# Conn_A.net
KiCad netlist of a schematic drawn in Altium Designer
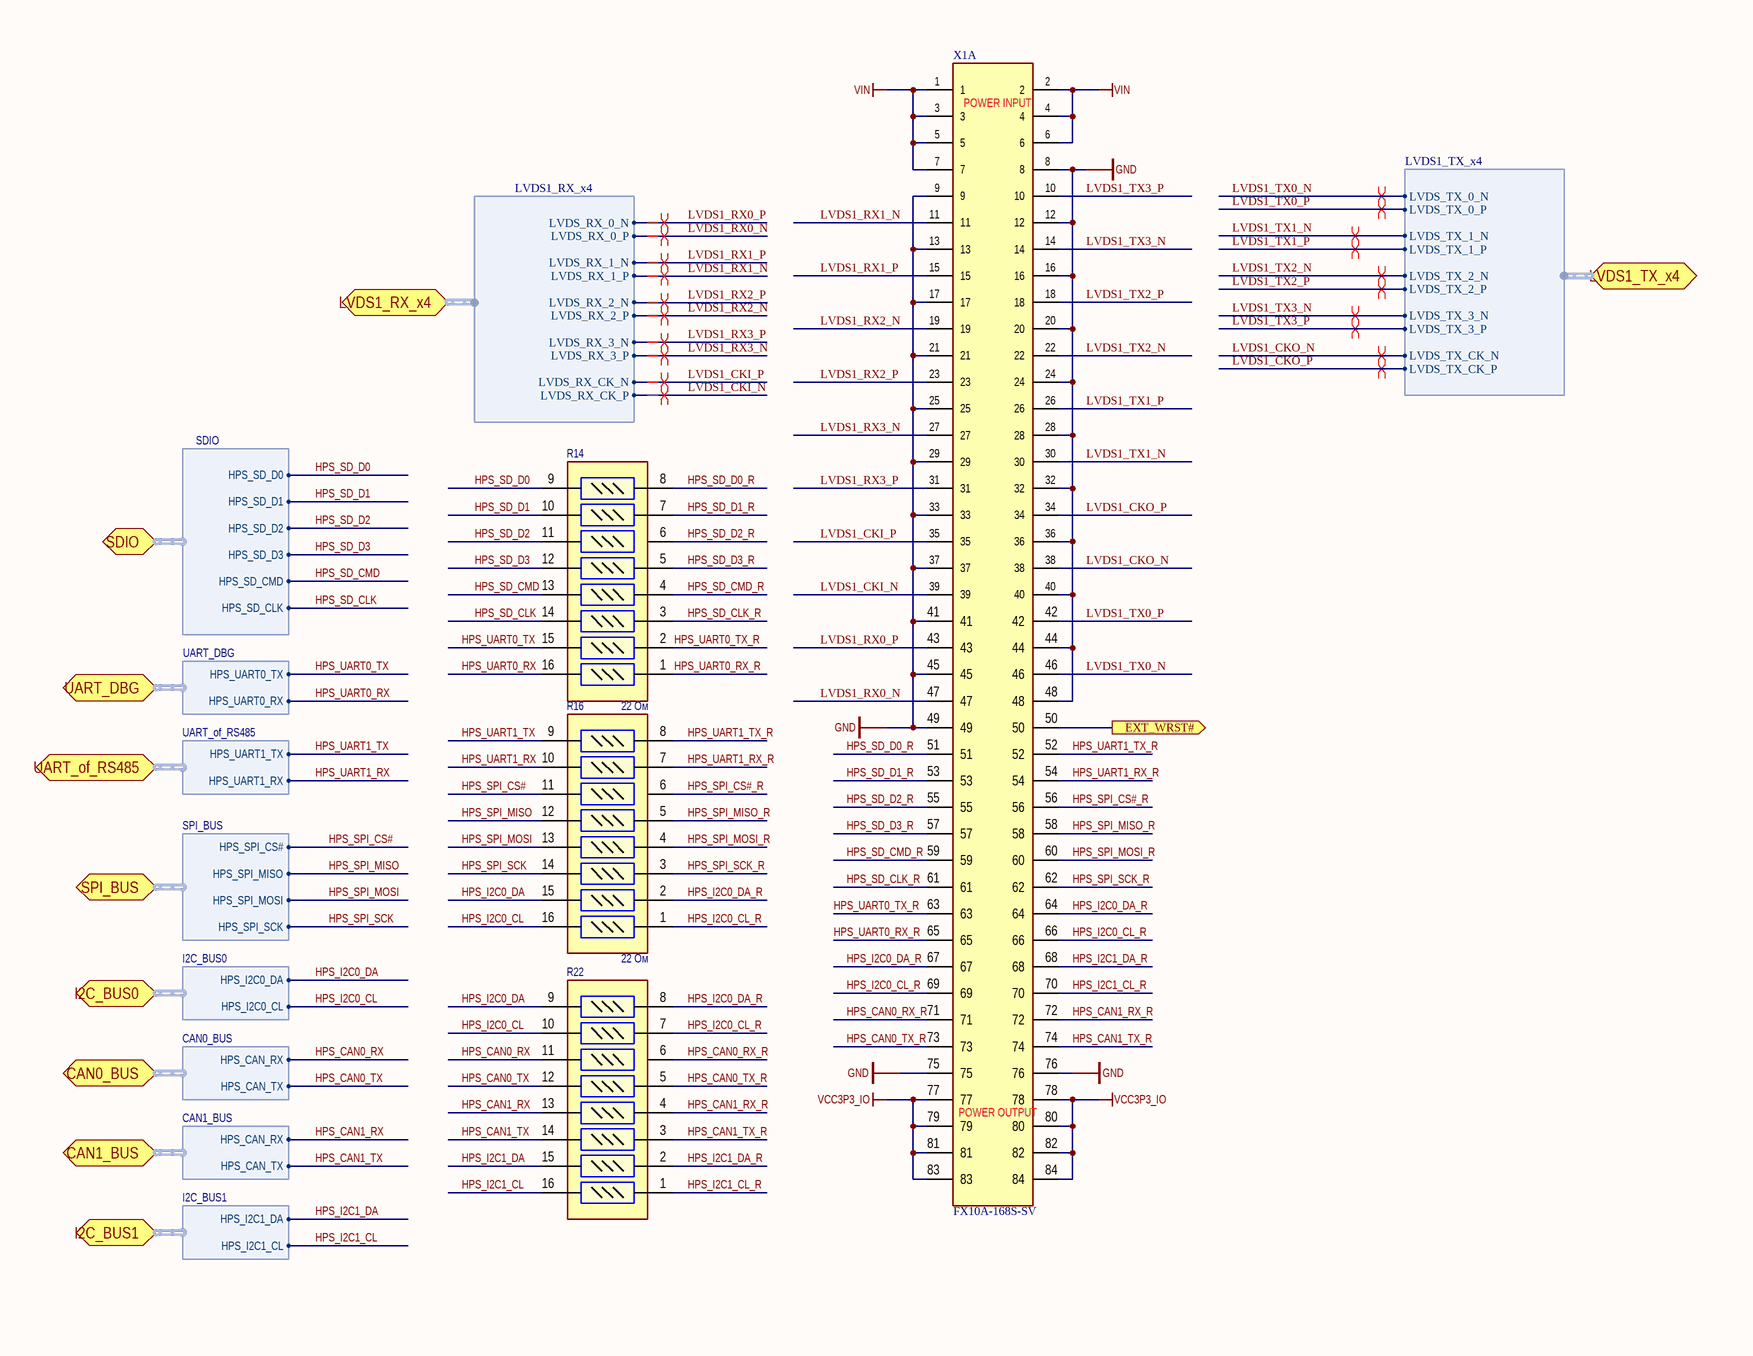
[diagram p0: Conn_A.SchDoc, left]
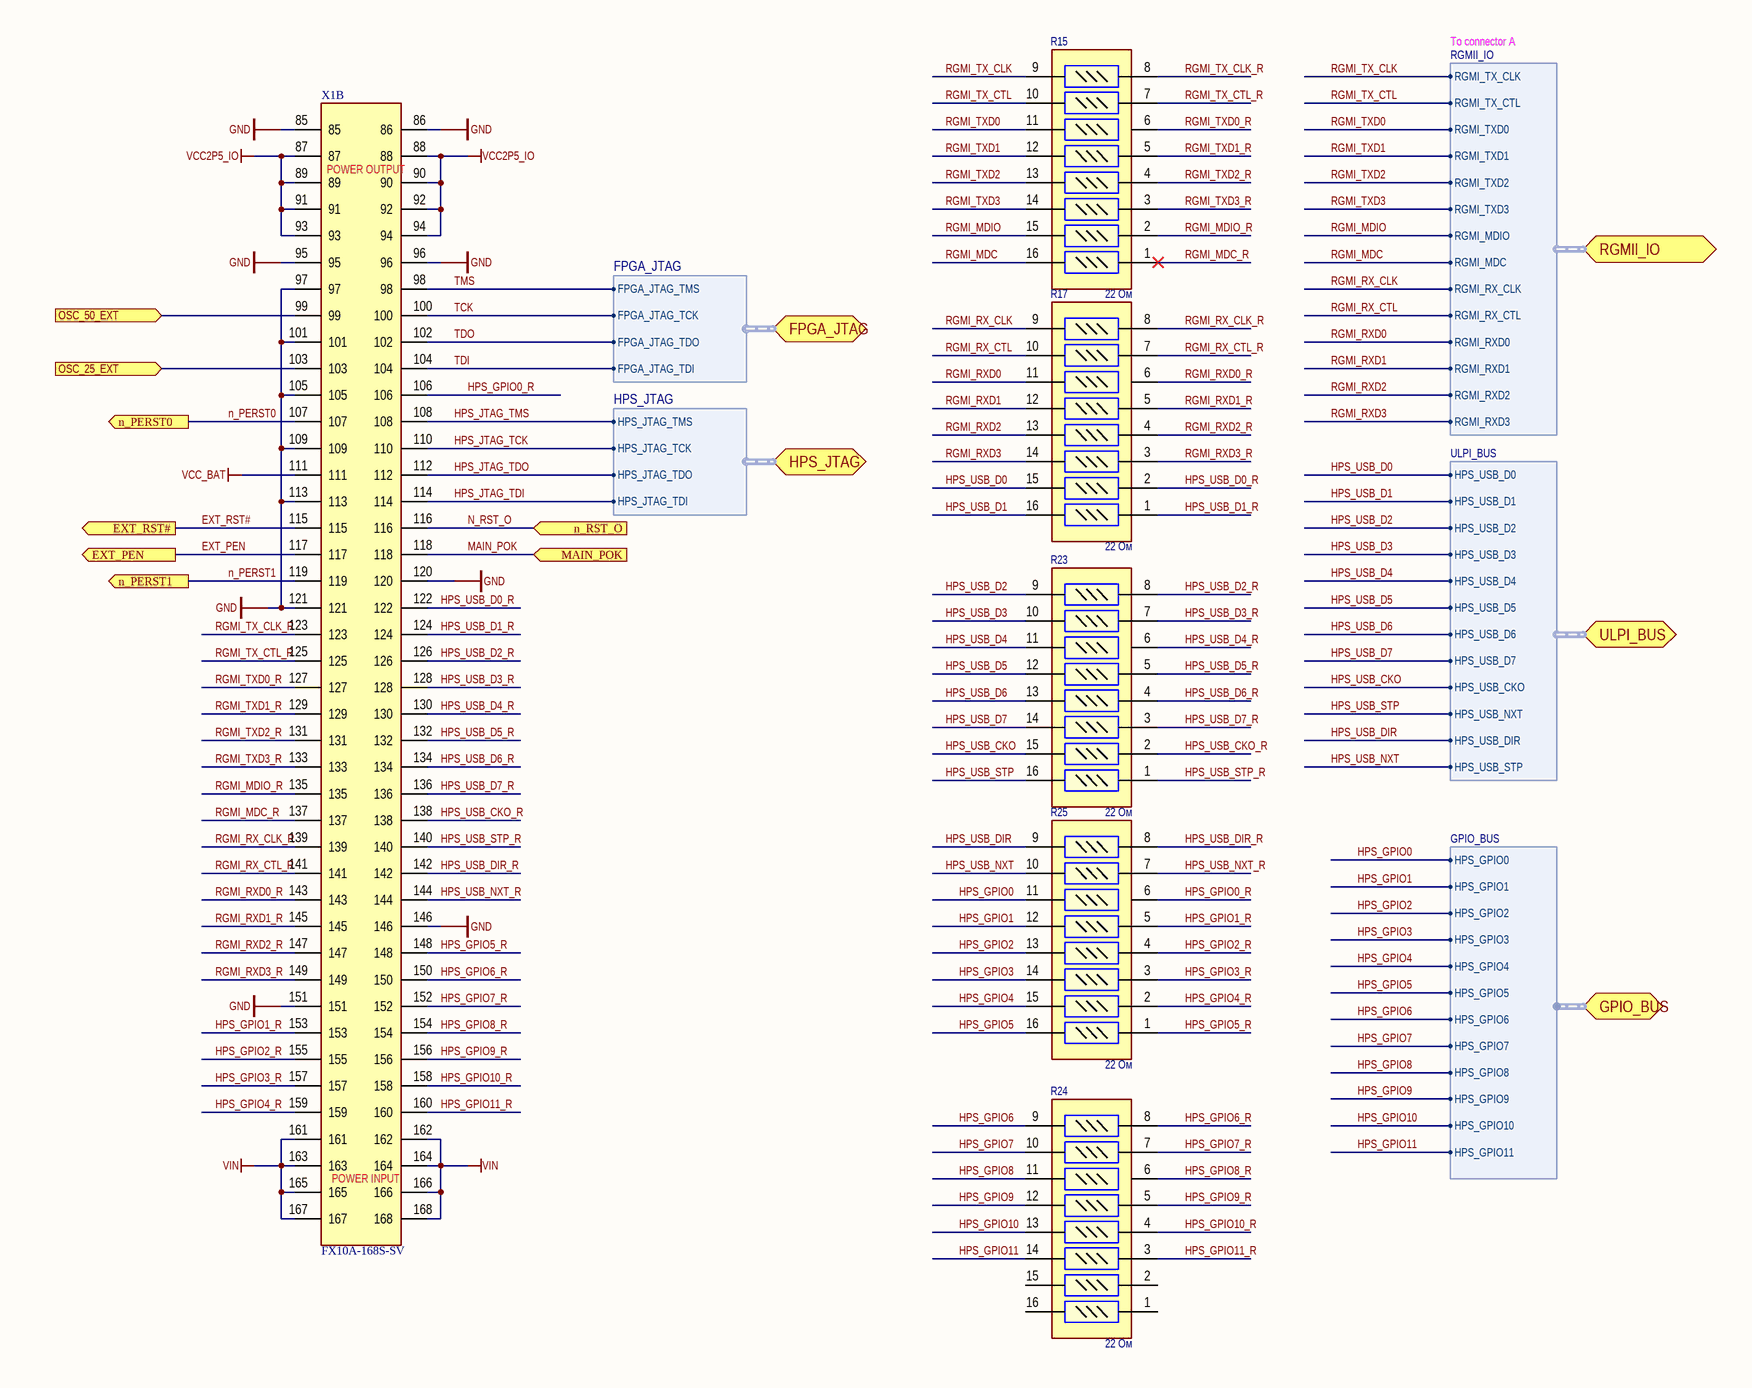
[diagram p1: Conn_A.SchDoc, right]

(export (version "E")
  (design (tool "Eeschema 10.0.6"))
  (components
    (comp (ref "R14")
      (value "22 Ом")
      (footprint "CAT16-J8")
      (description "Набор чип резисторов")
      (fields (field (name "Comment") "YC248-JR-07-22 Ом"))
      (libsource (lib "SD_IC") (part "YC248-JR-07-#"))
    )
    (comp (ref "R15")
      (value "22 Ом")
      (footprint "CAT16-J8")
      (description "Набор чип резисторов")
      (fields (field (name "Comment") "YC248-JR-07-22 Ом"))
      (libsource (lib "SD_IC") (part "YC248-JR-07-#"))
    )
    (comp (ref "R16")
      (value "22 Ом")
      (footprint "CAT16-J8")
      (description "Набор чип резисторов")
      (fields (field (name "Comment") "YC248-JR-07-22 Ом"))
      (libsource (lib "SD_IC") (part "YC248-JR-07-#"))
    )
    (comp (ref "R17")
      (value "22 Ом")
      (footprint "CAT16-J8")
      (description "Набор чип резисторов")
      (fields (field (name "Comment") "YC248-JR-07-22 Ом"))
      (libsource (lib "SD_IC") (part "YC248-JR-07-#"))
    )
    (comp (ref "R22")
      (value "YC248-JR-07-")
      (footprint "CAT16-J8")
      (description "Набор чип резисторов")
      (libsource (lib "SD_IC") (part "YC248-JR-07-#"))
    )
    (comp (ref "R23")
      (value "22 Ом")
      (footprint "CAT16-J8")
      (description "Набор чип резисторов")
      (fields (field (name "Comment") "YC248-JR-07-22 Ом"))
      (libsource (lib "SD_IC") (part "YC248-JR-07-#"))
    )
    (comp (ref "R24")
      (value "22 Ом")
      (footprint "CAT16-J8")
      (description "Набор чип резисторов")
      (fields (field (name "Comment") "YC248-JR-07-22 Ом"))
      (libsource (lib "SD_IC") (part "YC248-JR-07-#"))
    )
    (comp (ref "R25")
      (value "22 Ом")
      (footprint "CAT16-J8")
      (description "Набор чип резисторов")
      (fields (field (name "Comment") "YC248-JR-07-22 Ом"))
      (libsource (lib "SD_IC") (part "YC248-JR-07-#"))
    )
    (comp (ref "X1")
      (value "FX10A-168S-SV")
      (footprint "FX10A-168S-SV")
      (libsource (lib "SD_IC") (part "FX10A-168S-SV"))
    )
  )
  (nets
    (net (code "16") (name "/EXT_PEN") (class "Default")
      (node (ref "X1") (pin "117") (pinfunction "117_117") (pintype "passive"))
    )
    (net (code "17") (name "/EXT_RST#") (class "Default")
      (node (ref "X1") (pin "115") (pinfunction "115_115") (pintype "passive"))
    )
    (net (code "18") (name "/EXT_WRST#") (class "Default")
      (node (ref "X1") (pin "50") (pinfunction "50_50") (pintype "passive"))
    )
    (net (code "19") (name "/HPS_CAN0_RX") (class "Default")
      (node (ref "R22") (pin "11") (pintype "passive"))
    )
    (net (code "20") (name "/HPS_CAN0_RX_R") (class "Default")
      (node (ref "R22") (pin "6") (pintype "passive"))
      (node (ref "X1") (pin "71") (pinfunction "71_71") (pintype "passive"))
    )
    (net (code "21") (name "/HPS_CAN0_TX") (class "Default")
      (node (ref "R22") (pin "12") (pintype "passive"))
    )
    (net (code "22") (name "/HPS_CAN0_TX_R") (class "Default")
      (node (ref "R22") (pin "5") (pintype "passive"))
      (node (ref "X1") (pin "73") (pinfunction "73_73") (pintype "passive"))
    )
    (net (code "23") (name "/HPS_CAN1_RX") (class "Default")
      (node (ref "R22") (pin "13") (pintype "passive"))
    )
    (net (code "24") (name "/HPS_CAN1_RX_R") (class "Default")
      (node (ref "R22") (pin "4") (pintype "passive"))
      (node (ref "X1") (pin "72") (pinfunction "72_72") (pintype "passive"))
    )
    (net (code "25") (name "/HPS_CAN1_TX") (class "Default")
      (node (ref "R22") (pin "14") (pintype "passive"))
    )
    (net (code "26") (name "/HPS_CAN1_TX_R") (class "Default")
      (node (ref "R22") (pin "3") (pintype "passive"))
      (node (ref "X1") (pin "74") (pinfunction "74_74") (pintype "passive"))
    )
    (net (code "27") (name "/HPS_GPIO0") (class "Default") (node (ref "R25") (pin "11") (pintype "passive")))
    (net (code "28") (name "/HPS_GPIO0_R") (class "Default")
      (node (ref "R25") (pin "6") (pintype "passive"))
      (node (ref "X1") (pin "106") (pinfunction "106_106") (pintype "passive"))
    )
    (net (code "29") (name "/HPS_GPIO1") (class "Default") (node (ref "R25") (pin "12") (pintype "passive")))
    (net (code "30") (name "/HPS_GPIO1_R") (class "Default")
      (node (ref "R25") (pin "5") (pintype "passive"))
      (node (ref "X1") (pin "153") (pinfunction "153_153") (pintype "passive"))
    )
    (net (code "31") (name "/HPS_GPIO2") (class "Default") (node (ref "R25") (pin "13") (pintype "passive")))
    (net (code "32") (name "/HPS_GPIO2_R") (class "Default")
      (node (ref "R25") (pin "4") (pintype "passive"))
      (node (ref "X1") (pin "155") (pinfunction "155_155") (pintype "passive"))
    )
    (net (code "33") (name "/HPS_GPIO3") (class "Default") (node (ref "R25") (pin "14") (pintype "passive")))
    (net (code "34") (name "/HPS_GPIO3_R") (class "Default")
      (node (ref "R25") (pin "3") (pintype "passive"))
      (node (ref "X1") (pin "157") (pinfunction "157_157") (pintype "passive"))
    )
    (net (code "35") (name "/HPS_GPIO4") (class "Default") (node (ref "R25") (pin "15") (pintype "passive")))
    (net (code "36") (name "/HPS_GPIO4_R") (class "Default")
      (node (ref "R25") (pin "2") (pintype "passive"))
      (node (ref "X1") (pin "159") (pinfunction "159_159") (pintype "passive"))
    )
    (net (code "37") (name "/HPS_GPIO5") (class "Default") (node (ref "R25") (pin "16") (pintype "passive")))
    (net (code "38") (name "/HPS_GPIO5_R") (class "Default")
      (node (ref "R25") (pin "1") (pintype "passive"))
      (node (ref "X1") (pin "148") (pinfunction "148_148") (pintype "passive"))
    )
    (net (code "39") (name "/HPS_GPIO6") (class "Default") (node (ref "R24") (pin "9") (pintype "passive")))
    (net (code "40") (name "/HPS_GPIO6_R") (class "Default")
      (node (ref "R24") (pin "8") (pintype "passive"))
      (node (ref "X1") (pin "150") (pinfunction "150_150") (pintype "passive"))
    )
    (net (code "41") (name "/HPS_GPIO7") (class "Default") (node (ref "R24") (pin "10") (pintype "passive")))
    (net (code "42") (name "/HPS_GPIO7_R") (class "Default")
      (node (ref "R24") (pin "7") (pintype "passive"))
      (node (ref "X1") (pin "152") (pinfunction "152_152") (pintype "passive"))
    )
    (net (code "43") (name "/HPS_GPIO8") (class "Default") (node (ref "R24") (pin "11") (pintype "passive")))
    (net (code "44") (name "/HPS_GPIO8_R") (class "Default")
      (node (ref "R24") (pin "6") (pintype "passive"))
      (node (ref "X1") (pin "154") (pinfunction "154_154") (pintype "passive"))
    )
    (net (code "45") (name "/HPS_GPIO9") (class "Default") (node (ref "R24") (pin "12") (pintype "passive")))
    (net (code "46") (name "/HPS_GPIO9_R") (class "Default")
      (node (ref "R24") (pin "5") (pintype "passive"))
      (node (ref "X1") (pin "156") (pinfunction "156_156") (pintype "passive"))
    )
    (net (code "47") (name "/HPS_GPIO10") (class "Default") (node (ref "R24") (pin "13") (pintype "passive")))
    (net (code "48") (name "/HPS_GPIO10_R") (class "Default")
      (node (ref "R24") (pin "4") (pintype "passive"))
      (node (ref "X1") (pin "158") (pinfunction "158_158") (pintype "passive"))
    )
    (net (code "49") (name "/HPS_GPIO11") (class "Default") (node (ref "R24") (pin "14") (pintype "passive")))
    (net (code "50") (name "/HPS_GPIO11_R") (class "Default")
      (node (ref "R24") (pin "3") (pintype "passive"))
      (node (ref "X1") (pin "160") (pinfunction "160_160") (pintype "passive"))
    )
    (net (code "51") (name "/HPS_I2C0_CL") (class "Default")
      (node (ref "R16") (pin "16") (pintype "passive"))
      (node (ref "R22") (pin "10") (pintype "passive"))
    )
    (net (code "52") (name "/HPS_I2C0_CL_R") (class "Default")
      (node (ref "R16") (pin "1") (pintype "passive"))
      (node (ref "R22") (pin "7") (pintype "passive"))
      (node (ref "X1") (pin "66") (pinfunction "66_66") (pintype "passive"))
      (node (ref "X1") (pin "69") (pinfunction "69_69") (pintype "passive"))
    )
    (net (code "53") (name "/HPS_I2C0_DA") (class "Default")
      (node (ref "R16") (pin "15") (pintype "passive"))
      (node (ref "R22") (pin "9") (pintype "passive"))
    )
    (net (code "54") (name "/HPS_I2C0_DA_R") (class "Default")
      (node (ref "R16") (pin "2") (pintype "passive"))
      (node (ref "R22") (pin "8") (pintype "passive"))
      (node (ref "X1") (pin "64") (pinfunction "64_64") (pintype "passive"))
      (node (ref "X1") (pin "67") (pinfunction "67_67") (pintype "passive"))
    )
    (net (code "55") (name "/HPS_I2C1_CL") (class "Default")
      (node (ref "R22") (pin "16") (pintype "passive"))
    )
    (net (code "56") (name "/HPS_I2C1_CL_R") (class "Default")
      (node (ref "R22") (pin "1") (pintype "passive"))
      (node (ref "X1") (pin "70") (pinfunction "70_70") (pintype "passive"))
    )
    (net (code "57") (name "/HPS_I2C1_DA") (class "Default")
      (node (ref "R22") (pin "15") (pintype "passive"))
    )
    (net (code "58") (name "/HPS_I2C1_DA_R") (class "Default")
      (node (ref "R22") (pin "2") (pintype "passive"))
      (node (ref "X1") (pin "68") (pinfunction "68_68") (pintype "passive"))
    )
    (net (code "59") (name "/HPS_JTAG_TCK") (class "Default")
      (node (ref "X1") (pin "110") (pinfunction "110_110") (pintype "passive"))
    )
    (net (code "60") (name "/HPS_JTAG_TDI") (class "Default")
      (node (ref "X1") (pin "114") (pinfunction "114_114") (pintype "passive"))
    )
    (net (code "61") (name "/HPS_JTAG_TDO") (class "Default")
      (node (ref "X1") (pin "112") (pinfunction "112_112") (pintype "passive"))
    )
    (net (code "62") (name "/HPS_JTAG_TMS") (class "Default")
      (node (ref "X1") (pin "108") (pinfunction "108_108") (pintype "passive"))
    )
    (net (code "63") (name "/HPS_SD_CLK") (class "Default") (node (ref "R14") (pin "14") (pintype "passive")))
    (net (code "64") (name "/HPS_SD_CLK_R") (class "Default")
      (node (ref "R14") (pin "3") (pintype "passive"))
      (node (ref "X1") (pin "61") (pinfunction "61_61") (pintype "passive"))
    )
    (net (code "65") (name "/HPS_SD_CMD") (class "Default") (node (ref "R14") (pin "13") (pintype "passive")))
    (net (code "66") (name "/HPS_SD_CMD_R") (class "Default")
      (node (ref "R14") (pin "4") (pintype "passive"))
      (node (ref "X1") (pin "59") (pinfunction "59_59") (pintype "passive"))
    )
    (net (code "67") (name "/HPS_SD_D0") (class "Default") (node (ref "R14") (pin "9") (pintype "passive")))
    (net (code "68") (name "/HPS_SD_D0_R") (class "Default")
      (node (ref "R14") (pin "8") (pintype "passive"))
      (node (ref "X1") (pin "51") (pinfunction "51_51") (pintype "passive"))
    )
    (net (code "69") (name "/HPS_SD_D1") (class "Default") (node (ref "R14") (pin "10") (pintype "passive")))
    (net (code "70") (name "/HPS_SD_D1_R") (class "Default")
      (node (ref "R14") (pin "7") (pintype "passive"))
      (node (ref "X1") (pin "53") (pinfunction "53_53") (pintype "passive"))
    )
    (net (code "71") (name "/HPS_SD_D2") (class "Default") (node (ref "R14") (pin "11") (pintype "passive")))
    (net (code "72") (name "/HPS_SD_D2_R") (class "Default")
      (node (ref "R14") (pin "6") (pintype "passive"))
      (node (ref "X1") (pin "55") (pinfunction "55_55") (pintype "passive"))
    )
    (net (code "73") (name "/HPS_SD_D3") (class "Default") (node (ref "R14") (pin "12") (pintype "passive")))
    (net (code "74") (name "/HPS_SD_D3_R") (class "Default")
      (node (ref "R14") (pin "5") (pintype "passive"))
      (node (ref "X1") (pin "57") (pinfunction "57_57") (pintype "passive"))
    )
    (net (code "75") (name "/HPS_SPI_CS#") (class "Default")
      (node (ref "R16") (pin "11") (pintype "passive"))
    )
    (net (code "76") (name "/HPS_SPI_CS#_R") (class "Default")
      (node (ref "R16") (pin "6") (pintype "passive"))
      (node (ref "X1") (pin "56") (pinfunction "56_56") (pintype "passive"))
    )
    (net (code "77") (name "/HPS_SPI_MISO") (class "Default")
      (node (ref "R16") (pin "12") (pintype "passive"))
    )
    (net (code "78") (name "/HPS_SPI_MISO_R") (class "Default")
      (node (ref "R16") (pin "5") (pintype "passive"))
      (node (ref "X1") (pin "58") (pinfunction "58_58") (pintype "passive"))
    )
    (net (code "79") (name "/HPS_SPI_MOSI") (class "Default")
      (node (ref "R16") (pin "13") (pintype "passive"))
    )
    (net (code "80") (name "/HPS_SPI_MOSI_R") (class "Default")
      (node (ref "R16") (pin "4") (pintype "passive"))
      (node (ref "X1") (pin "60") (pinfunction "60_60") (pintype "passive"))
    )
    (net (code "81") (name "/HPS_SPI_SCK") (class "Default")
      (node (ref "R16") (pin "14") (pintype "passive"))
    )
    (net (code "82") (name "/HPS_SPI_SCK_R") (class "Default")
      (node (ref "R16") (pin "3") (pintype "passive"))
      (node (ref "X1") (pin "62") (pinfunction "62_62") (pintype "passive"))
    )
    (net (code "83") (name "/HPS_UART0_RX") (class "Default")
      (node (ref "R14") (pin "16") (pintype "passive"))
    )
    (net (code "84") (name "/HPS_UART0_RX_R") (class "Default")
      (node (ref "R14") (pin "1") (pintype "passive"))
      (node (ref "X1") (pin "65") (pinfunction "65_65") (pintype "passive"))
    )
    (net (code "85") (name "/HPS_UART0_TX") (class "Default")
      (node (ref "R14") (pin "15") (pintype "passive"))
    )
    (net (code "86") (name "/HPS_UART0_TX_R") (class "Default")
      (node (ref "R14") (pin "2") (pintype "passive"))
      (node (ref "X1") (pin "63") (pinfunction "63_63") (pintype "passive"))
    )
    (net (code "87") (name "/HPS_UART1_RX") (class "Default")
      (node (ref "R16") (pin "10") (pintype "passive"))
    )
    (net (code "88") (name "/HPS_UART1_RX_R") (class "Default")
      (node (ref "R16") (pin "7") (pintype "passive"))
      (node (ref "X1") (pin "54") (pinfunction "54_54") (pintype "passive"))
    )
    (net (code "89") (name "/HPS_UART1_TX") (class "Default")
      (node (ref "R16") (pin "9") (pintype "passive"))
    )
    (net (code "90") (name "/HPS_UART1_TX_R") (class "Default")
      (node (ref "R16") (pin "8") (pintype "passive"))
      (node (ref "X1") (pin "52") (pinfunction "52_52") (pintype "passive"))
    )
    (net (code "91") (name "/HPS_USB_CKO") (class "Default")
      (node (ref "R23") (pin "15") (pintype "passive"))
    )
    (net (code "92") (name "/HPS_USB_CKO_R") (class "Default")
      (node (ref "R23") (pin "2") (pintype "passive"))
      (node (ref "X1") (pin "138") (pinfunction "138_138") (pintype "passive"))
    )
    (net (code "93") (name "/HPS_USB_D0") (class "Default") (node (ref "R17") (pin "15") (pintype "passive")))
    (net (code "94") (name "/HPS_USB_D0_R") (class "Default")
      (node (ref "R17") (pin "2") (pintype "passive"))
      (node (ref "X1") (pin "122") (pinfunction "122_122") (pintype "passive"))
    )
    (net (code "95") (name "/HPS_USB_D1") (class "Default") (node (ref "R17") (pin "16") (pintype "passive")))
    (net (code "96") (name "/HPS_USB_D1_R") (class "Default")
      (node (ref "R17") (pin "1") (pintype "passive"))
      (node (ref "X1") (pin "124") (pinfunction "124_124") (pintype "passive"))
    )
    (net (code "97") (name "/HPS_USB_D2") (class "Default") (node (ref "R23") (pin "9") (pintype "passive")))
    (net (code "98") (name "/HPS_USB_D2_R") (class "Default")
      (node (ref "R23") (pin "8") (pintype "passive"))
      (node (ref "X1") (pin "126") (pinfunction "126_126") (pintype "passive"))
    )
    (net (code "99") (name "/HPS_USB_D3") (class "Default") (node (ref "R23") (pin "10") (pintype "passive")))
    (net (code "100") (name "/HPS_USB_D3_R") (class "Default")
      (node (ref "R23") (pin "7") (pintype "passive"))
      (node (ref "X1") (pin "128") (pinfunction "128_128") (pintype "passive"))
    )
    (net (code "101") (name "/HPS_USB_D4") (class "Default")
      (node (ref "R23") (pin "11") (pintype "passive"))
    )
    (net (code "102") (name "/HPS_USB_D4_R") (class "Default")
      (node (ref "R23") (pin "6") (pintype "passive"))
      (node (ref "X1") (pin "130") (pinfunction "130_130") (pintype "passive"))
    )
    (net (code "103") (name "/HPS_USB_D5") (class "Default")
      (node (ref "R23") (pin "12") (pintype "passive"))
    )
    (net (code "104") (name "/HPS_USB_D5_R") (class "Default")
      (node (ref "R23") (pin "5") (pintype "passive"))
      (node (ref "X1") (pin "132") (pinfunction "132_132") (pintype "passive"))
    )
    (net (code "105") (name "/HPS_USB_D6") (class "Default")
      (node (ref "R23") (pin "13") (pintype "passive"))
    )
    (net (code "106") (name "/HPS_USB_D6_R") (class "Default")
      (node (ref "R23") (pin "4") (pintype "passive"))
      (node (ref "X1") (pin "134") (pinfunction "134_134") (pintype "passive"))
    )
    (net (code "107") (name "/HPS_USB_D7") (class "Default")
      (node (ref "R23") (pin "14") (pintype "passive"))
    )
    (net (code "108") (name "/HPS_USB_D7_R") (class "Default")
      (node (ref "R23") (pin "3") (pintype "passive"))
      (node (ref "X1") (pin "136") (pinfunction "136_136") (pintype "passive"))
    )
    (net (code "109") (name "/HPS_USB_DIR") (class "Default")
      (node (ref "R25") (pin "9") (pintype "passive"))
    )
    (net (code "110") (name "/HPS_USB_DIR_R") (class "Default")
      (node (ref "R25") (pin "8") (pintype "passive"))
      (node (ref "X1") (pin "142") (pinfunction "142_142") (pintype "passive"))
    )
    (net (code "111") (name "/HPS_USB_NXT") (class "Default")
      (node (ref "R25") (pin "10") (pintype "passive"))
    )
    (net (code "112") (name "/HPS_USB_NXT_R") (class "Default")
      (node (ref "R25") (pin "7") (pintype "passive"))
      (node (ref "X1") (pin "144") (pinfunction "144_144") (pintype "passive"))
    )
    (net (code "113") (name "/HPS_USB_STP") (class "Default")
      (node (ref "R23") (pin "16") (pintype "passive"))
    )
    (net (code "114") (name "/HPS_USB_STP_R") (class "Default")
      (node (ref "R23") (pin "1") (pintype "passive"))
      (node (ref "X1") (pin "140") (pinfunction "140_140") (pintype "passive"))
    )
    (net (code "115") (name "/LVDS1_CKI_N") (class "Default")
      (node (ref "X1") (pin "39") (pinfunction "39_39") (pintype "passive"))
    )
    (net (code "116") (name "/LVDS1_CKI_P") (class "Default")
      (node (ref "X1") (pin "35") (pinfunction "35_35") (pintype "passive"))
    )
    (net (code "117") (name "/LVDS1_CKO_N") (class "Default")
      (node (ref "X1") (pin "38") (pinfunction "38_38") (pintype "passive"))
    )
    (net (code "118") (name "/LVDS1_CKO_P") (class "Default")
      (node (ref "X1") (pin "34") (pinfunction "34_34") (pintype "passive"))
    )
    (net (code "119") (name "/LVDS1_RX0_N") (class "Default")
      (node (ref "X1") (pin "47") (pinfunction "47_47") (pintype "passive"))
    )
    (net (code "120") (name "/LVDS1_RX0_P") (class "Default")
      (node (ref "X1") (pin "43") (pinfunction "43_43") (pintype "passive"))
    )
    (net (code "121") (name "/LVDS1_RX1_N") (class "Default")
      (node (ref "X1") (pin "11") (pinfunction "11_11") (pintype "passive"))
    )
    (net (code "122") (name "/LVDS1_RX1_P") (class "Default")
      (node (ref "X1") (pin "15") (pinfunction "15_15") (pintype "passive"))
    )
    (net (code "123") (name "/LVDS1_RX2_N") (class "Default")
      (node (ref "X1") (pin "19") (pinfunction "19_19") (pintype "passive"))
    )
    (net (code "124") (name "/LVDS1_RX2_P") (class "Default")
      (node (ref "X1") (pin "23") (pinfunction "23_23") (pintype "passive"))
    )
    (net (code "125") (name "/LVDS1_RX3_N") (class "Default")
      (node (ref "X1") (pin "27") (pinfunction "27_27") (pintype "passive"))
    )
    (net (code "126") (name "/LVDS1_RX3_P") (class "Default")
      (node (ref "X1") (pin "31") (pinfunction "31_31") (pintype "passive"))
    )
    (net (code "127") (name "/LVDS1_TX0_N") (class "Default")
      (node (ref "X1") (pin "46") (pinfunction "46_46") (pintype "passive"))
    )
    (net (code "128") (name "/LVDS1_TX0_P") (class "Default")
      (node (ref "X1") (pin "42") (pinfunction "42_42") (pintype "passive"))
    )
    (net (code "129") (name "/LVDS1_TX1_N") (class "Default")
      (node (ref "X1") (pin "30") (pinfunction "30_30") (pintype "passive"))
    )
    (net (code "130") (name "/LVDS1_TX1_P") (class "Default")
      (node (ref "X1") (pin "26") (pinfunction "26_26") (pintype "passive"))
    )
    (net (code "131") (name "/LVDS1_TX2_N") (class "Default")
      (node (ref "X1") (pin "22") (pinfunction "22_22") (pintype "passive"))
    )
    (net (code "132") (name "/LVDS1_TX2_P") (class "Default")
      (node (ref "X1") (pin "18") (pinfunction "18_18") (pintype "passive"))
    )
    (net (code "133") (name "/LVDS1_TX3_N") (class "Default")
      (node (ref "X1") (pin "14") (pinfunction "14_14") (pintype "passive"))
    )
    (net (code "134") (name "/LVDS1_TX3_P") (class "Default")
      (node (ref "X1") (pin "10") (pinfunction "10_10") (pintype "passive"))
    )
    (net (code "135") (name "/MAIN_POK") (class "Default")
      (node (ref "X1") (pin "118") (pinfunction "118_118") (pintype "passive"))
    )
    (net (code "136") (name "/N_RST_O") (class "Default")
      (node (ref "X1") (pin "116") (pinfunction "116_116") (pintype "passive"))
    )
    (net (code "137") (name "/OSC_25_EXT") (class "Default")
      (node (ref "X1") (pin "103") (pinfunction "103_103") (pintype "passive"))
    )
    (net (code "138") (name "/OSC_50_EXT") (class "Default")
      (node (ref "X1") (pin "99") (pinfunction "99_99") (pintype "passive"))
    )
    (net (code "139") (name "/RGMI_MDC") (class "Default") (node (ref "R15") (pin "16") (pintype "passive")))
    (net (code "140") (name "/RGMI_MDC_R") (class "Default")
      (node (ref "R15") (pin "1") (pintype "passive"))
      (node (ref "X1") (pin "137") (pinfunction "137_137") (pintype "passive"))
    )
    (net (code "141") (name "/RGMI_MDIO") (class "Default") (node (ref "R15") (pin "15") (pintype "passive")))
    (net (code "142") (name "/RGMI_MDIO_R") (class "Default")
      (node (ref "R15") (pin "2") (pintype "passive"))
      (node (ref "X1") (pin "135") (pinfunction "135_135") (pintype "passive"))
    )
    (net (code "143") (name "/RGMI_RXD0") (class "Default") (node (ref "R17") (pin "11") (pintype "passive")))
    (net (code "144") (name "/RGMI_RXD0_R") (class "Default")
      (node (ref "R17") (pin "6") (pintype "passive"))
      (node (ref "X1") (pin "143") (pinfunction "143_143") (pintype "passive"))
    )
    (net (code "145") (name "/RGMI_RXD1") (class "Default") (node (ref "R17") (pin "12") (pintype "passive")))
    (net (code "146") (name "/RGMI_RXD1_R") (class "Default")
      (node (ref "R17") (pin "5") (pintype "passive"))
      (node (ref "X1") (pin "145") (pinfunction "145_145") (pintype "passive"))
    )
    (net (code "147") (name "/RGMI_RXD2") (class "Default") (node (ref "R17") (pin "13") (pintype "passive")))
    (net (code "148") (name "/RGMI_RXD2_R") (class "Default")
      (node (ref "R17") (pin "4") (pintype "passive"))
      (node (ref "X1") (pin "147") (pinfunction "147_147") (pintype "passive"))
    )
    (net (code "149") (name "/RGMI_RXD3") (class "Default") (node (ref "R17") (pin "14") (pintype "passive")))
    (net (code "150") (name "/RGMI_RXD3_R") (class "Default")
      (node (ref "R17") (pin "3") (pintype "passive"))
      (node (ref "X1") (pin "149") (pinfunction "149_149") (pintype "passive"))
    )
    (net (code "151") (name "/RGMI_RX_CLK") (class "Default")
      (node (ref "R17") (pin "9") (pintype "passive"))
    )
    (net (code "152") (name "/RGMI_RX_CLK_R") (class "Default")
      (node (ref "R17") (pin "8") (pintype "passive"))
      (node (ref "X1") (pin "139") (pinfunction "139_139") (pintype "passive"))
    )
    (net (code "153") (name "/RGMI_RX_CTL") (class "Default")
      (node (ref "R17") (pin "10") (pintype "passive"))
    )
    (net (code "154") (name "/RGMI_RX_CTL_R") (class "Default")
      (node (ref "R17") (pin "7") (pintype "passive"))
      (node (ref "X1") (pin "141") (pinfunction "141_141") (pintype "passive"))
    )
    (net (code "155") (name "/RGMI_TXD0") (class "Default") (node (ref "R15") (pin "11") (pintype "passive")))
    (net (code "156") (name "/RGMI_TXD0_R") (class "Default")
      (node (ref "R15") (pin "6") (pintype "passive"))
      (node (ref "X1") (pin "127") (pinfunction "127_127") (pintype "passive"))
    )
    (net (code "157") (name "/RGMI_TXD1") (class "Default") (node (ref "R15") (pin "12") (pintype "passive")))
    (net (code "158") (name "/RGMI_TXD1_R") (class "Default")
      (node (ref "R15") (pin "5") (pintype "passive"))
      (node (ref "X1") (pin "129") (pinfunction "129_129") (pintype "passive"))
    )
    (net (code "159") (name "/RGMI_TXD2") (class "Default") (node (ref "R15") (pin "13") (pintype "passive")))
    (net (code "160") (name "/RGMI_TXD2_R") (class "Default")
      (node (ref "R15") (pin "4") (pintype "passive"))
      (node (ref "X1") (pin "131") (pinfunction "131_131") (pintype "passive"))
    )
    (net (code "161") (name "/RGMI_TXD3") (class "Default") (node (ref "R15") (pin "14") (pintype "passive")))
    (net (code "162") (name "/RGMI_TXD3_R") (class "Default")
      (node (ref "R15") (pin "3") (pintype "passive"))
      (node (ref "X1") (pin "133") (pinfunction "133_133") (pintype "passive"))
    )
    (net (code "163") (name "/RGMI_TX_CLK") (class "Default")
      (node (ref "R15") (pin "9") (pintype "passive"))
    )
    (net (code "164") (name "/RGMI_TX_CLK_R") (class "Default")
      (node (ref "R15") (pin "8") (pintype "passive"))
      (node (ref "X1") (pin "123") (pinfunction "123_123") (pintype "passive"))
    )
    (net (code "165") (name "/RGMI_TX_CTL") (class "Default")
      (node (ref "R15") (pin "10") (pintype "passive"))
    )
    (net (code "166") (name "/RGMI_TX_CTL_R") (class "Default")
      (node (ref "R15") (pin "7") (pintype "passive"))
      (node (ref "X1") (pin "125") (pinfunction "125_125") (pintype "passive"))
    )
    (net (code "167") (name "/TCK") (class "Default")
      (node (ref "X1") (pin "100") (pinfunction "100_100") (pintype "passive"))
    )
    (net (code "168") (name "/TDI") (class "Default")
      (node (ref "X1") (pin "104") (pinfunction "104_104") (pintype "passive"))
    )
    (net (code "169") (name "/TDO") (class "Default")
      (node (ref "X1") (pin "102") (pinfunction "102_102") (pintype "passive"))
    )
    (net (code "170") (name "/TMS") (class "Default")
      (node (ref "X1") (pin "98") (pinfunction "98_98") (pintype "passive"))
    )
    (net (code "171") (name "/n_PERST0") (class "Default")
      (node (ref "X1") (pin "107") (pinfunction "107_107") (pintype "passive"))
    )
    (net (code "172") (name "/n_PERST1") (class "Default")
      (node (ref "X1") (pin "119") (pinfunction "119_119") (pintype "passive"))
    )
    (net (code "188") (name "GND") (class "Default")
      (node (ref "X1") (pin "101") (pinfunction "101_101") (pintype "passive"))
      (node (ref "X1") (pin "105") (pinfunction "105_105") (pintype "passive"))
      (node (ref "X1") (pin "109") (pinfunction "109_109") (pintype "passive"))
      (node (ref "X1") (pin "113") (pinfunction "113_113") (pintype "passive"))
      (node (ref "X1") (pin "12") (pinfunction "12_12") (pintype "passive"))
      (node (ref "X1") (pin "120") (pinfunction "120_120") (pintype "passive"))
      (node (ref "X1") (pin "121") (pinfunction "121_121") (pintype "passive"))
      (node (ref "X1") (pin "13") (pinfunction "13_13") (pintype "passive"))
      (node (ref "X1") (pin "146") (pinfunction "146_146") (pintype "passive"))
      (node (ref "X1") (pin "151") (pinfunction "151_151") (pintype "passive"))
      (node (ref "X1") (pin "16") (pinfunction "16_16") (pintype "passive"))
      (node (ref "X1") (pin "17") (pinfunction "17_17") (pintype "passive"))
      (node (ref "X1") (pin "20") (pinfunction "20_20") (pintype "passive"))
      (node (ref "X1") (pin "21") (pinfunction "21_21") (pintype "passive"))
      (node (ref "X1") (pin "24") (pinfunction "24_24") (pintype "passive"))
      (node (ref "X1") (pin "25") (pinfunction "25_25") (pintype "passive"))
      (node (ref "X1") (pin "28") (pinfunction "28_28") (pintype "passive"))
      (node (ref "X1") (pin "29") (pinfunction "29_29") (pintype "passive"))
      (node (ref "X1") (pin "32") (pinfunction "32_32") (pintype "passive"))
      (node (ref "X1") (pin "33") (pinfunction "33_33") (pintype "passive"))
      (node (ref "X1") (pin "36") (pinfunction "36_36") (pintype "passive"))
      (node (ref "X1") (pin "37") (pinfunction "37_37") (pintype "passive"))
      (node (ref "X1") (pin "40") (pinfunction "40_40") (pintype "passive"))
      (node (ref "X1") (pin "41") (pinfunction "41_41") (pintype "passive"))
      (node (ref "X1") (pin "44") (pinfunction "44_44") (pintype "passive"))
      (node (ref "X1") (pin "45") (pinfunction "45_45") (pintype "passive"))
      (node (ref "X1") (pin "48") (pinfunction "48_48") (pintype "passive"))
      (node (ref "X1") (pin "49") (pinfunction "49_49") (pintype "passive"))
      (node (ref "X1") (pin "75") (pinfunction "75_75") (pintype "passive"))
      (node (ref "X1") (pin "76") (pinfunction "76_76") (pintype "passive"))
      (node (ref "X1") (pin "8") (pinfunction "8_8") (pintype "passive"))
      (node (ref "X1") (pin "85") (pinfunction "85_85") (pintype "passive"))
      (node (ref "X1") (pin "86") (pinfunction "86_86") (pintype "passive"))
      (node (ref "X1") (pin "9") (pinfunction "9_9") (pintype "passive"))
      (node (ref "X1") (pin "95") (pinfunction "95_95") (pintype "passive"))
      (node (ref "X1") (pin "96") (pinfunction "96_96") (pintype "passive"))
      (node (ref "X1") (pin "97") (pinfunction "97_97") (pintype "passive"))
    )
    (net (code "189") (name "VCC2P5_IO") (class "Default")
      (node (ref "X1") (pin "87") (pinfunction "87_87") (pintype "passive"))
      (node (ref "X1") (pin "88") (pinfunction "88_88") (pintype "passive"))
      (node (ref "X1") (pin "89") (pinfunction "89_89") (pintype "passive"))
      (node (ref "X1") (pin "90") (pinfunction "90_90") (pintype "passive"))
      (node (ref "X1") (pin "91") (pinfunction "91_91") (pintype "passive"))
      (node (ref "X1") (pin "92") (pinfunction "92_92") (pintype "passive"))
      (node (ref "X1") (pin "93") (pinfunction "93_93") (pintype "passive"))
      (node (ref "X1") (pin "94") (pinfunction "94_94") (pintype "passive"))
    )
    (net (code "190") (name "VCC3P3_IO") (class "Default")
      (node (ref "X1") (pin "77") (pinfunction "77_77") (pintype "passive"))
      (node (ref "X1") (pin "78") (pinfunction "78_78") (pintype "passive"))
      (node (ref "X1") (pin "79") (pinfunction "79_79") (pintype "passive"))
      (node (ref "X1") (pin "80") (pinfunction "80_80") (pintype "passive"))
      (node (ref "X1") (pin "81") (pinfunction "81_81") (pintype "passive"))
      (node (ref "X1") (pin "82") (pinfunction "82_82") (pintype "passive"))
      (node (ref "X1") (pin "83") (pinfunction "83_83") (pintype "passive"))
      (node (ref "X1") (pin "84") (pinfunction "84_84") (pintype "passive"))
    )
    (net (code "191") (name "VCC_BAT") (class "Default")
      (node (ref "X1") (pin "111") (pinfunction "111_111") (pintype "passive"))
    )
    (net (code "192") (name "VIN") (class "Default")
      (node (ref "X1") (pin "1") (pinfunction "1_1") (pintype "passive"))
      (node (ref "X1") (pin "161") (pinfunction "161_161") (pintype "passive"))
      (node (ref "X1") (pin "162") (pinfunction "162_162") (pintype "passive"))
      (node (ref "X1") (pin "163") (pinfunction "163_163") (pintype "passive"))
      (node (ref "X1") (pin "164") (pinfunction "164_164") (pintype "passive"))
      (node (ref "X1") (pin "165") (pinfunction "165_165") (pintype "passive"))
      (node (ref "X1") (pin "166") (pinfunction "166_166") (pintype "passive"))
      (node (ref "X1") (pin "167") (pinfunction "167_167") (pintype "passive"))
      (node (ref "X1") (pin "168") (pinfunction "168_168") (pintype "passive"))
      (node (ref "X1") (pin "2") (pinfunction "2_2") (pintype "passive"))
      (node (ref "X1") (pin "3") (pinfunction "3_3") (pintype "passive"))
      (node (ref "X1") (pin "4") (pinfunction "4_4") (pintype "passive"))
      (node (ref "X1") (pin "5") (pinfunction "5_5") (pintype "passive"))
      (node (ref "X1") (pin "6") (pinfunction "6_6") (pintype "passive"))
      (node (ref "X1") (pin "7") (pinfunction "7_7") (pintype "passive"))
    )
    (net (code "193") (name "unconnected-(R24-Pad1)") (class "Default")
      (node (ref "R24") (pin "1") (pintype "passive"))
    )
    (net (code "194") (name "unconnected-(R24-Pad2)") (class "Default")
      (node (ref "R24") (pin "2") (pintype "passive"))
    )
    (net (code "195") (name "unconnected-(R24-Pad15)") (class "Default")
      (node (ref "R24") (pin "15") (pintype "passive"))
    )
    (net (code "196") (name "unconnected-(R24-Pad16)") (class "Default")
      (node (ref "R24") (pin "16") (pintype "passive"))
    )
  )
)
